# Amplifier_Sheet.net
KiCad netlist of a schematic drawn in Altium Designer
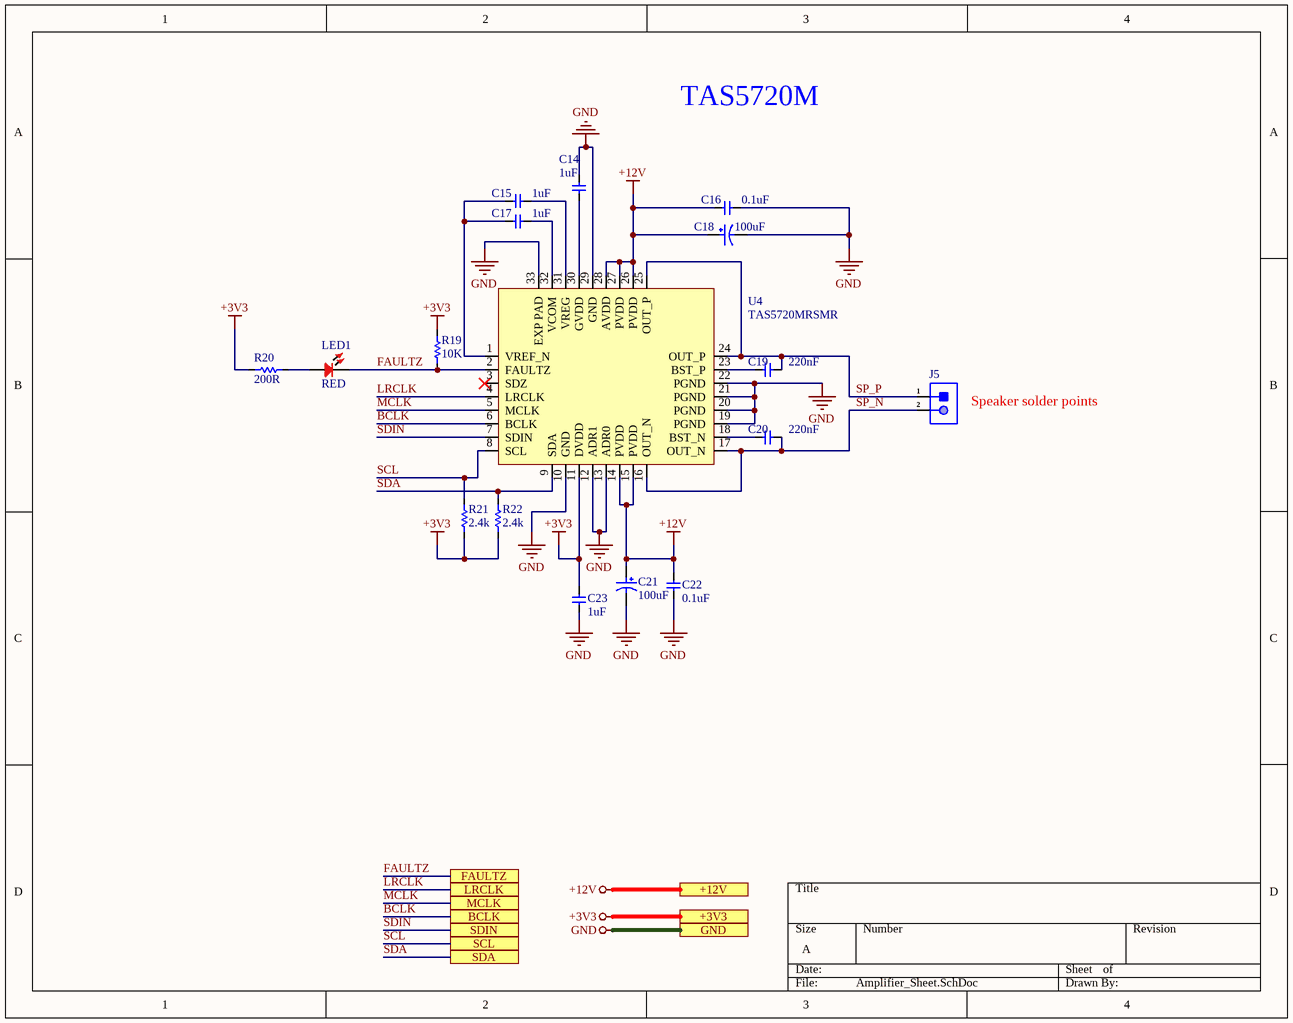
[diagram p0: Amplifier_Sheet.SchDoc]

(export (version "E")
  (design (tool "Eeschema 10.0.6"))
  (components
    (comp (ref "C14")
      (value "1uF")
      (footprint "Cap-0603")
      (description "CAP CER 1UF 25V X5R 0603")
      (fields
        (field (name "MANUFACTURER") "Yageo")
        (field (name "MANUFACTURER PART NUMBER") "CC0603KRX5R8BB105")
      )
      (libsource (lib "DigitalAzanClock") (part "CC0603KRX5R8BB105"))
    )
    (comp (ref "C15")
      (value "1uF")
      (footprint "Cap-0603")
      (description "CAP CER 1UF 25V X5R 0603")
      (fields
        (field (name "MANUFACTURER") "Yageo")
        (field (name "MANUFACTURER PART NUMBER") "CC0603KRX5R8BB105")
      )
      (libsource (lib "DigitalAzanClock") (part "CC0603KRX5R8BB105"))
    )
    (comp (ref "C16")
      (value "0.1uF")
      (footprint "Cap-0603")
      (description "CAP CER 0.1UF 100V X7R 0603")
      (fields
        (field (name "MANUFACTURER") "Yageo")
        (field (name "MANUFACTURER PART NUMBER") "CC0603KRX7R0BB104")
      )
      (libsource (lib "DigitalAzanClock") (part "CC0603KRX7R0BB104"))
    )
    (comp (ref "C17")
      (value "1uF")
      (footprint "Cap-0603")
      (description "CAP CER 1UF 25V X5R 0603")
      (fields
        (field (name "MANUFACTURER") "Yageo")
        (field (name "MANUFACTURER PART NUMBER") "CC0603KRX5R8BB105")
      )
      (libsource (lib "DigitalAzanClock") (part "CC0603KRX5R8BB105"))
    )
    (comp (ref "C18")
      (value "100uF")
      (footprint "RVT1H101M0607")
      (description "100uF 50V ±20% SMD,D6.3xL7.7mm Aluminum Electrolytic Capacitors - SMD ROHS")
      (fields
        (field (name "MANUFACTURER") "ROQANG")
        (field (name "MANUFACTURER PART NUMBER") "RVT1H101M0607")
      )
      (libsource (lib "") (part "RVT1H101M0607_1"))
    )
    (comp (ref "C19")
      (value "220nF")
      (footprint "Cap-0402")
      (description "CAP CER 0.22UF 25V X5R 0402")
      (fields
        (field (name "MANUFACTURER") "Yageo")
        (field (name "MANUFACTURER PART NUMBER") "CC0402KRX5R8BB224")
      )
      (libsource (lib "DigitalAzanClock") (part "CC0402KRX5R8BB224"))
    )
    (comp (ref "C20")
      (value "220nF")
      (footprint "Cap-0402")
      (description "CAP CER 0.22UF 25V X5R 0402")
      (fields
        (field (name "MANUFACTURER") "Yageo")
        (field (name "MANUFACTURER PART NUMBER") "CC0402KRX5R8BB224")
      )
      (libsource (lib "DigitalAzanClock") (part "CC0402KRX5R8BB224"))
    )
    (comp (ref "C21")
      (value "100uF")
      (footprint "RVT1H101M0607")
      (description "100uF 50V ±20% SMD,D6.3xL7.7mm Aluminum Electrolytic Capacitors - SMD ROHS")
      (fields
        (field (name "MANUFACTURER") "ROQANG")
        (field (name "MANUFACTURER PART NUMBER") "RVT1H101M0607")
      )
      (libsource (lib "DigitalAzanClock") (part "RVT1H101M0607"))
    )
    (comp (ref "C22")
      (value "0.1uF")
      (footprint "Cap-0603")
      (description "CAP CER 0.1UF 100V X7R 0603")
      (fields
        (field (name "MANUFACTURER") "Yageo")
        (field (name "MANUFACTURER PART NUMBER") "CC0603KRX7R0BB104")
      )
      (libsource (lib "DigitalAzanClock") (part "CC0603KRX7R0BB104"))
    )
    (comp (ref "C23")
      (value "1uF")
      (footprint "Cap-0603")
      (description "CAP CER 1UF 25V X5R 0603")
      (fields
        (field (name "MANUFACTURER") "Yageo")
        (field (name "MANUFACTURER PART NUMBER") "CC0603KRX5R8BB105")
      )
      (libsource (lib "DigitalAzanClock") (part "CC0603KRX5R8BB105"))
    )
    (comp (ref "J5")
      (value "2P THrough Hole Pads")
      (footprint "2P THrough Hole Pads")
      (description "Wire Connecting Pad")
      (libsource (lib "DigitalAzanClock") (part "2P THrough Hole Pads"))
    )
    (comp (ref "LED1")
      (value "RED")
      (footprint "LED-0603")
      (description "RED LED 0603 Light Emitting Diodes")
      (fields
        (field (name "MANUFACTURER") "Foshan NationStar Optoelectronics")
        (field (name "MANUFACTURER PART NUMBER") "NCD0603R3")
      )
      (libsource (lib "DigitalAzanClock") (part "NCD0603R3"))
    )
    (comp (ref "R19")
      (value "10K")
      (footprint "Res-0603")
      (description "RES SMD 10K OHM 0.1% 1/10W 0603")
      (fields
        (field (name "MANUFACTURER") "Yageo")
        (field (name "MANUFACTURER PART NUMBER") "RT0603BRD0710KL")
      )
      (libsource (lib "DigitalAzanClock") (part "RT0603BRD0710KL"))
    )
    (comp (ref "R20")
      (value "200R")
      (footprint "Res-0402")
      (description "RES 200 OHM 1% 1/16W 0402")
      (fields
        (field (name "MANUFACTURER") "Yageo")
        (field (name "MANUFACTURER PART NUMBER") "RC0402FR-07200RL")
      )
      (libsource (lib "DigitalAzanClock") (part "RC0402FR-07200RL"))
    )
    (comp (ref "R21")
      (value "2.4k")
      (footprint "Res-0402")
      (description "RES 2.4K OHM 1% 1/16W 0402")
      (fields
        (field (name "MANUFACTURER") "Yageo")
        (field (name "MANUFACTURER PART NUMBER") "RC0402FR-072K4L")
      )
      (libsource (lib "DigitalAzanClock") (part "RC0402FR-072K4L"))
    )
    (comp (ref "R22")
      (value "2.4k")
      (footprint "Res-0402")
      (description "RES 2.4K OHM 1% 1/16W 0402")
      (fields
        (field (name "MANUFACTURER") "Yageo")
        (field (name "MANUFACTURER PART NUMBER") "RC0402FR-072K4L")
      )
      (libsource (lib "DigitalAzanClock") (part "RC0402FR-072K4L"))
    )
    (comp (ref "U4")
      (value "TAS5720MRSMR")
      (footprint "TAS5720M")
      (description "20Wx1@4Ω VQFN-32(4x4) Audio Power OpAmps ROHS")
      (fields (field (name "MANUFACTURER") "Texas Instruments") (field (name "LCSC PART NUMBER") "C5214961"))
      (libsource (lib "DigitalAzanClock") (part "TAS5720MRSMR"))
    )
  )
  (nets
    (net (code "1") (name "+3V3") (class "Default")
      (node (ref "C23") (pin "2") (pinfunction "2_2") (pintype "passive"))
      (node (ref "R19") (pin "1") (pinfunction "1_1") (pintype "passive"))
      (node (ref "R20") (pin "1") (pinfunction "1_1") (pintype "passive"))
      (node (ref "R21") (pin "1") (pinfunction "1_1") (pintype "passive"))
      (node (ref "R22") (pin "1") (pinfunction "1_1") (pintype "passive"))
      (node (ref "U4") (pin "11") (pinfunction "DVDD_11") (pintype "passive"))
    )
    (net (code "2") (name "+12V") (class "Default")
      (node (ref "C16") (pin "1") (pinfunction "1_1") (pintype "passive"))
      (node (ref "C18") (pin "1") (pintype "passive"))
      (node (ref "C21") (pin "1") (pintype "passive"))
      (node (ref "C22") (pin "1") (pinfunction "1_1") (pintype "passive"))
      (node (ref "U4") (pin "14") (pinfunction "PVDD_14") (pintype "passive"))
      (node (ref "U4") (pin "15") (pinfunction "PVDD_15") (pintype "passive"))
      (node (ref "U4") (pin "26") (pinfunction "PVDD_26") (pintype "passive"))
      (node (ref "U4") (pin "27") (pinfunction "PVDD_27") (pintype "passive"))
      (node (ref "U4") (pin "28") (pinfunction "AVDD_28") (pintype "passive"))
    )
    (net (code "3") (name "/BCLK") (class "Default")
      (node (ref "U4") (pin "6") (pinfunction "BCLK_6") (pintype "passive"))
    )
    (net (code "4") (name "/FAULTZ") (class "Default")
      (node (ref "LED1") (pin "2") (pinfunction "2_2") (pintype "passive"))
      (node (ref "R19") (pin "2") (pinfunction "2_2") (pintype "passive"))
      (node (ref "U4") (pin "2") (pinfunction "FAULTZ_2") (pintype "passive"))
    )
    (net (code "5") (name "/LRCLK") (class "Default")
      (node (ref "U4") (pin "4") (pinfunction "LRCLK_4") (pintype "passive"))
    )
    (net (code "6") (name "/MCLK") (class "Default")
      (node (ref "U4") (pin "5") (pinfunction "MCLK_5") (pintype "passive"))
    )
    (net (code "7") (name "/SCL") (class "Default")
      (node (ref "R21") (pin "2") (pinfunction "2_2") (pintype "passive"))
      (node (ref "U4") (pin "8") (pinfunction "SCL_8") (pintype "passive"))
    )
    (net (code "8") (name "/SDA") (class "Default")
      (node (ref "R22") (pin "2") (pinfunction "2_2") (pintype "passive"))
      (node (ref "U4") (pin "9") (pinfunction "SDA_9") (pintype "passive"))
    )
    (net (code "9") (name "/SDIN") (class "Default")
      (node (ref "U4") (pin "7") (pinfunction "SDIN_7") (pintype "passive"))
    )
    (net (code "10") (name "/SP_N") (class "Default")
      (node (ref "C20") (pin "2") (pinfunction "2_2") (pintype "passive"))
      (node (ref "J5") (pin "2") (pinfunction "2_2") (pintype "passive"))
      (node (ref "U4") (pin "16") (pinfunction "OUT_N_16") (pintype "passive"))
      (node (ref "U4") (pin "17") (pinfunction "OUT_N_17") (pintype "passive"))
    )
    (net (code "11") (name "/SP_P") (class "Default")
      (node (ref "C19") (pin "2") (pinfunction "2_2") (pintype "passive"))
      (node (ref "J5") (pin "1") (pinfunction "1_1") (pintype "passive"))
      (node (ref "U4") (pin "24") (pinfunction "OUT_P_24") (pintype "passive"))
      (node (ref "U4") (pin "25") (pinfunction "OUT_P_25") (pintype "passive"))
    )
    (net (code "12") (name "GND") (class "Default")
      (node (ref "C14") (pin "2") (pinfunction "2_2") (pintype "passive"))
      (node (ref "C16") (pin "2") (pinfunction "2_2") (pintype "passive"))
      (node (ref "C18") (pin "2") (pintype "passive"))
      (node (ref "C21") (pin "2") (pintype "passive"))
      (node (ref "C22") (pin "2") (pinfunction "2_2") (pintype "passive"))
      (node (ref "C23") (pin "1") (pinfunction "1_1") (pintype "passive"))
      (node (ref "U4") (pin "10") (pinfunction "GND_10") (pintype "passive"))
      (node (ref "U4") (pin "12") (pinfunction "ADR1_12") (pintype "passive"))
      (node (ref "U4") (pin "13") (pinfunction "ADR0_13") (pintype "passive"))
      (node (ref "U4") (pin "19") (pinfunction "PGND_19") (pintype "passive"))
      (node (ref "U4") (pin "20") (pinfunction "PGND_20") (pintype "passive"))
      (node (ref "U4") (pin "21") (pinfunction "PGND_21") (pintype "passive"))
      (node (ref "U4") (pin "22") (pinfunction "PGND_22") (pintype "passive"))
      (node (ref "U4") (pin "29") (pinfunction "GND_29") (pintype "passive"))
      (node (ref "U4") (pin "33") (pinfunction "EXP_PAD_33") (pintype "passive"))
    )
    (net (code "13") (name "Net-(LED1-Pad1)") (class "Default")
      (node (ref "LED1") (pin "1") (pinfunction "1_1") (pintype "passive"))
      (node (ref "R20") (pin "2") (pinfunction "2_2") (pintype "passive"))
    )
    (net (code "14") (name "Net-(U4-BST_N)") (class "Default")
      (node (ref "C20") (pin "1") (pinfunction "1_1") (pintype "passive"))
      (node (ref "U4") (pin "18") (pinfunction "BST_N_18") (pintype "passive"))
    )
    (net (code "15") (name "Net-(U4-BST_P)") (class "Default")
      (node (ref "C19") (pin "1") (pinfunction "1_1") (pintype "passive"))
      (node (ref "U4") (pin "23") (pinfunction "BST_P_23") (pintype "passive"))
    )
    (net (code "16") (name "Net-(U4-GVDD)") (class "Default")
      (node (ref "C14") (pin "1") (pinfunction "1_1") (pintype "passive"))
      (node (ref "U4") (pin "30") (pinfunction "GVDD_30") (pintype "passive"))
    )
    (net (code "17") (name "Net-(U4-VCOM)") (class "Default")
      (node (ref "C17") (pin "2") (pinfunction "2_2") (pintype "passive"))
      (node (ref "U4") (pin "32") (pinfunction "VCOM_32") (pintype "passive"))
    )
    (net (code "18") (name "Net-(U4-VREF_N)") (class "Default")
      (node (ref "C15") (pin "1") (pinfunction "1_1") (pintype "passive"))
      (node (ref "C17") (pin "1") (pinfunction "1_1") (pintype "passive"))
      (node (ref "U4") (pin "1") (pinfunction "VREF_N_1") (pintype "passive"))
    )
    (net (code "19") (name "Net-(U4-VREG)") (class "Default")
      (node (ref "C15") (pin "2") (pinfunction "2_2") (pintype "passive"))
      (node (ref "U4") (pin "31") (pinfunction "VREG_31") (pintype "passive"))
    )
    (net (code "20") (name "unconnected-(U4-SDZ-Pad3)") (class "Default")
      (node (ref "U4") (pin "3") (pinfunction "SDZ_3") (pintype "passive+no_connect"))
    )
  )
)
